# IB_V2_MOSFET.net
KiCad netlist of a schematic drawn in Altium Designer
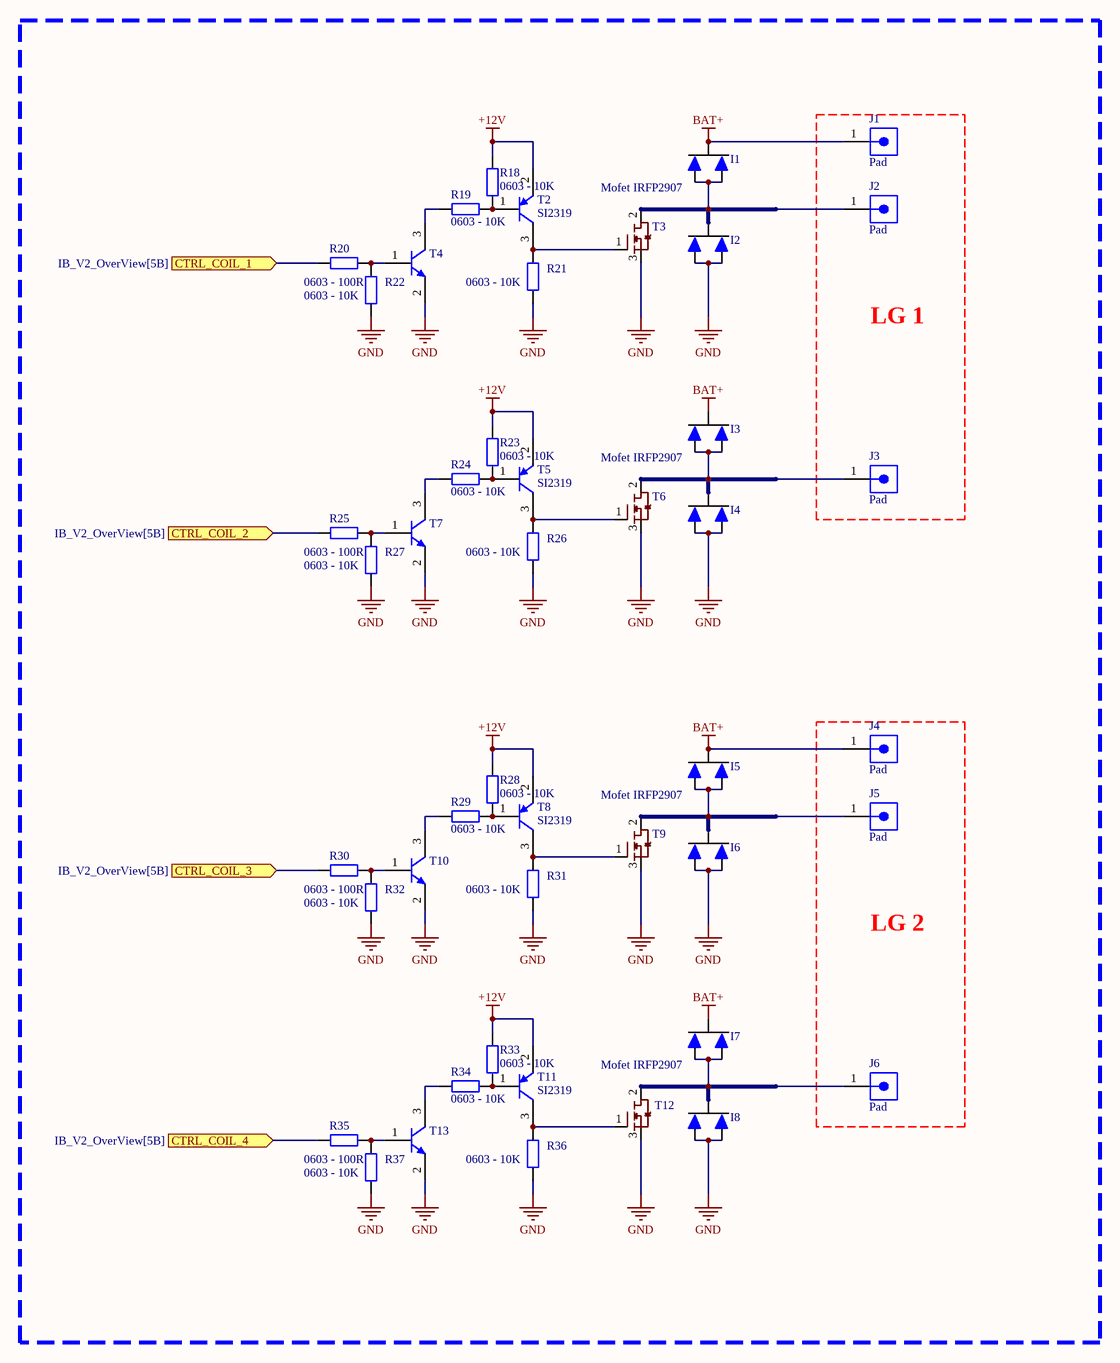
[diagram p0: IB_V2_MOSFET.SchDoc]

(export (version "E")
  (design (tool "Eeschema 10.0.6"))
  (components
    (comp (ref "I1")
      (value "12CWQ10FN")
      (footprint "TO-252")
      (description "Diode Schottky 100V 12A, SMD DPAK")
      (libsource (lib "Mach HTD-K54") (part "Diode - 12CWQ10FN"))
    )
    (comp (ref "I2")
      (value "12CWQ10FN")
      (footprint "TO-252")
      (description "Diode Schottky 100V 12A, SMD DPAK")
      (libsource (lib "Mach HTD-K54") (part "Diode - 12CWQ10FN"))
    )
    (comp (ref "I3")
      (value "12CWQ10FN")
      (footprint "TO-252")
      (description "Diode Schottky 100V 12A, SMD DPAK")
      (libsource (lib "Mach HTD-K54") (part "Diode - 12CWQ10FN"))
    )
    (comp (ref "I4")
      (value "12CWQ10FN")
      (footprint "TO-252")
      (description "Diode Schottky 100V 12A, SMD DPAK")
      (libsource (lib "Mach HTD-K54") (part "Diode - 12CWQ10FN"))
    )
    (comp (ref "I5")
      (value "12CWQ10FN")
      (footprint "TO-252")
      (description "Diode Schottky 100V 12A, SMD DPAK")
      (libsource (lib "Mach HTD-K54") (part "Diode - 12CWQ10FN"))
    )
    (comp (ref "I6")
      (value "12CWQ10FN")
      (footprint "TO-252")
      (description "Diode Schottky 100V 12A, SMD DPAK")
      (libsource (lib "Mach HTD-K54") (part "Diode - 12CWQ10FN"))
    )
    (comp (ref "I7")
      (value "12CWQ10FN")
      (footprint "TO-252")
      (description "Diode Schottky 100V 12A, SMD DPAK")
      (libsource (lib "Mach HTD-K54") (part "Diode - 12CWQ10FN"))
    )
    (comp (ref "I8")
      (value "12CWQ10FN")
      (footprint "TO-252")
      (description "Diode Schottky 100V 12A, SMD DPAK")
      (libsource (lib "Mach HTD-K54") (part "Diode - 12CWQ10FN"))
    )
    (comp (ref "J1")
      (value "Pad")
      (footprint "pad_4.5x4.5_hole_2.5mm")
      (fields (field (name "PUBLISHER") "Altium Limited"))
      (libsource (lib "MinhTien_SCHLib") (part "Pad"))
    )
    (comp (ref "J2")
      (value "Pad")
      (footprint "pad_4.5x4.5_hole_2.5mm")
      (fields (field (name "PUBLISHER") "Altium Limited"))
      (libsource (lib "MinhTien_SCHLib") (part "Pad"))
    )
    (comp (ref "J3")
      (value "Pad")
      (footprint "pad_4.5x4.5_hole_2.5mm")
      (fields (field (name "PUBLISHER") "Altium Limited"))
      (libsource (lib "MinhTien_SCHLib") (part "Pad"))
    )
    (comp (ref "J4")
      (value "Pad")
      (footprint "pad_4.5x4.5_hole_2.5mm")
      (fields (field (name "PUBLISHER") "Altium Limited"))
      (libsource (lib "MinhTien_SCHLib") (part "Pad"))
    )
    (comp (ref "J5")
      (value "Pad")
      (footprint "pad_4.5x4.5_hole_2.5mm")
      (fields (field (name "PUBLISHER") "Altium Limited"))
      (libsource (lib "MinhTien_SCHLib") (part "Pad"))
    )
    (comp (ref "J6")
      (value "Pad")
      (footprint "pad_4.5x4.5_hole_2.5mm")
      (fields (field (name "PUBLISHER") "Altium Limited"))
      (libsource (lib "MinhTien_SCHLib") (part "Pad"))
    )
    (comp (ref "R18")
      (value "0603 - 10K")
      (footprint "tro smd 0603")
      (description "Dán")
      (libsource (lib "Altium_Lib_by_KhueNguyenCreator") (part "Tro 0603 1% 680R"))
    )
    (comp (ref "R19")
      (value "0603 - 10K")
      (footprint "tro smd 0603")
      (description "Dán")
      (libsource (lib "Altium_Lib_by_KhueNguyenCreator") (part "Tro 0603 1% 680R"))
    )
    (comp (ref "R20")
      (value "0603 - 100R")
      (footprint "tro smd 0603")
      (description "Dán")
      (libsource (lib "Altium_Lib_by_KhueNguyenCreator") (part "Tro 0603 1% 680R"))
    )
    (comp (ref "R21")
      (value "0603 - 10K")
      (footprint "tro smd 0603")
      (description "Dán")
      (libsource (lib "Altium_Lib_by_KhueNguyenCreator") (part "Tro 0603 1% 680R"))
    )
    (comp (ref "R22")
      (value "0603 - 10K")
      (footprint "tro smd 0603")
      (description "Dán")
      (libsource (lib "Altium_Lib_by_KhueNguyenCreator") (part "Tro 0603 1% 680R"))
    )
    (comp (ref "R23")
      (value "0603 - 10K")
      (footprint "tro smd 0603")
      (description "Dán")
      (libsource (lib "Altium_Lib_by_KhueNguyenCreator") (part "Tro 0603 1% 680R"))
    )
    (comp (ref "R24")
      (value "0603 - 10K")
      (footprint "tro smd 0603")
      (description "Dán")
      (libsource (lib "Altium_Lib_by_KhueNguyenCreator") (part "Tro 0603 1% 680R"))
    )
    (comp (ref "R25")
      (value "0603 - 100R")
      (footprint "tro smd 0603")
      (description "Dán")
      (libsource (lib "Altium_Lib_by_KhueNguyenCreator") (part "Tro 0603 1% 680R"))
    )
    (comp (ref "R26")
      (value "0603 - 10K")
      (footprint "tro smd 0603")
      (description "Dán")
      (libsource (lib "Altium_Lib_by_KhueNguyenCreator") (part "Tro 0603 1% 680R"))
    )
    (comp (ref "R27")
      (value "0603 - 10K")
      (footprint "tro smd 0603")
      (description "Dán")
      (libsource (lib "Altium_Lib_by_KhueNguyenCreator") (part "Tro 0603 1% 680R"))
    )
    (comp (ref "R28")
      (value "0603 - 10K")
      (footprint "tro smd 0603")
      (description "Dán")
      (libsource (lib "Altium_Lib_by_KhueNguyenCreator") (part "Tro 0603 1% 680R"))
    )
    (comp (ref "R29")
      (value "0603 - 10K")
      (footprint "tro smd 0603")
      (description "Dán")
      (libsource (lib "Altium_Lib_by_KhueNguyenCreator") (part "Tro 0603 1% 680R"))
    )
    (comp (ref "R30")
      (value "0603 - 100R")
      (footprint "tro smd 0603")
      (description "Dán")
      (libsource (lib "Altium_Lib_by_KhueNguyenCreator") (part "Tro 0603 1% 680R"))
    )
    (comp (ref "R31")
      (value "0603 - 10K")
      (footprint "tro smd 0603")
      (description "Dán")
      (libsource (lib "Altium_Lib_by_KhueNguyenCreator") (part "Tro 0603 1% 680R"))
    )
    (comp (ref "R32")
      (value "0603 - 10K")
      (footprint "tro smd 0603")
      (description "Dán")
      (libsource (lib "Altium_Lib_by_KhueNguyenCreator") (part "Tro 0603 1% 680R"))
    )
    (comp (ref "R33")
      (value "0603 - 10K")
      (footprint "tro smd 0603")
      (description "Dán")
      (libsource (lib "Altium_Lib_by_KhueNguyenCreator") (part "Tro 0603 1% 680R"))
    )
    (comp (ref "R34")
      (value "0603 - 10K")
      (footprint "tro smd 0603")
      (description "Dán")
      (libsource (lib "Altium_Lib_by_KhueNguyenCreator") (part "Tro 0603 1% 680R"))
    )
    (comp (ref "R35")
      (value "0603 - 100R")
      (footprint "tro smd 0603")
      (description "Dán")
      (libsource (lib "Altium_Lib_by_KhueNguyenCreator") (part "Tro 0603 1% 680R"))
    )
    (comp (ref "R36")
      (value "0603 - 10K")
      (footprint "tro smd 0603")
      (description "Dán")
      (libsource (lib "Altium_Lib_by_KhueNguyenCreator") (part "Tro 0603 1% 680R"))
    )
    (comp (ref "R37")
      (value "0603 - 10K")
      (footprint "tro smd 0603")
      (description "Dán")
      (libsource (lib "Altium_Lib_by_KhueNguyenCreator") (part "Tro 0603 1% 680R"))
    )
    (comp (ref "T2")
      (value "SI2319")
      (footprint "SOT - 23")
      (description "P-Channel 40-V(D-S) MOSEFET\r\nSOT-23/3 LEAD")
      (libsource (lib "HTD-AK") (part "Transistor - A1015"))
    )
    (comp (ref "T3")
      (value "Mofet IRFP2907")
      (footprint "TO 247 AC")
      (libsource (lib "TG21_SCHLib") (part "IRFP2907"))
    )
    (comp (ref "T4")
      (value "MMBT2222A 1P Transistor NPN")
      (footprint "SOT - 23")
      (description "Transistor NPN 40V 0.6A 3 Chân SOT-23/3 LEAD")
      (libsource (lib "HTD-AK") (part "Transistor - 2N2222"))
    )
    (comp (ref "T5")
      (value "SI2319")
      (footprint "SOT - 23")
      (description "P-Channel 40-V(D-S) MOSEFET\r\nSOT-23/3 LEAD")
      (libsource (lib "HTD-AK") (part "Transistor - A1015"))
    )
    (comp (ref "T6")
      (value "Mofet IRFP2907")
      (footprint "TO 247 AC")
      (libsource (lib "TG21_SCHLib") (part "IRFP2907"))
    )
    (comp (ref "T7")
      (value "MMBT2222A 1P Transistor NPN")
      (footprint "SOT - 23")
      (description "Transistor NPN 40V 0.6A 3 Chân SOT-23/3 LEAD")
      (libsource (lib "HTD-AK") (part "Transistor - 2N2222"))
    )
    (comp (ref "T8")
      (value "SI2319")
      (footprint "SOT - 23")
      (description "P-Channel 40-V(D-S) MOSEFET\r\nSOT-23/3 LEAD")
      (libsource (lib "HTD-AK") (part "Transistor - A1015"))
    )
    (comp (ref "T9")
      (value "Mofet IRFP2907")
      (footprint "TO 247 AC")
      (libsource (lib "TG21_SCHLib") (part "IRFP2907"))
    )
    (comp (ref "T10")
      (value "MMBT2222A 1P Transistor NPN")
      (footprint "SOT - 23")
      (description "Transistor NPN 40V 0.6A 3 Chân SOT-23/3 LEAD")
      (libsource (lib "HTD-AK") (part "Transistor - 2N2222"))
    )
    (comp (ref "T11")
      (value "SI2319")
      (footprint "SOT - 23")
      (description "P-Channel 40-V(D-S) MOSEFET\r\nSOT-23/3 LEAD")
      (libsource (lib "HTD-AK") (part "Transistor - A1015"))
    )
    (comp (ref "T12")
      (value "Mofet IRFP2907")
      (footprint "TO 247 AC")
      (libsource (lib "TG21_SCHLib") (part "IRFP2907"))
    )
    (comp (ref "T13")
      (value "MMBT2222A 1P Transistor NPN")
      (footprint "SOT - 23")
      (description "Transistor NPN 40V 0.6A 3 Chân SOT-23/3 LEAD")
      (libsource (lib "HTD-AK") (part "Transistor - 2N2222"))
    )
  )
  (nets
    (net (code "1") (name "+12V") (class "Default")
      (node (ref "R18") (pin "1") (pinfunction "1_1") (pintype "passive"))
      (node (ref "R23") (pin "1") (pinfunction "1_1") (pintype "passive"))
      (node (ref "R28") (pin "1") (pinfunction "1_1") (pintype "passive"))
      (node (ref "R33") (pin "1") (pinfunction "1_1") (pintype "passive"))
      (node (ref "T11") (pin "2") (pinfunction "E_2") (pintype "passive"))
      (node (ref "T2") (pin "2") (pinfunction "E_2") (pintype "passive"))
      (node (ref "T5") (pin "2") (pinfunction "E_2") (pintype "passive"))
      (node (ref "T8") (pin "2") (pinfunction "E_2") (pintype "passive"))
    )
    (net (code "2") (name "/CTRL_COIL_1") (class "Default")
      (node (ref "R20") (pin "2") (pinfunction "2_2") (pintype "passive"))
    )
    (net (code "3") (name "/CTRL_COIL_2") (class "Default")
      (node (ref "R25") (pin "2") (pinfunction "2_2") (pintype "passive"))
    )
    (net (code "4") (name "/CTRL_COIL_3") (class "Default")
      (node (ref "R30") (pin "2") (pinfunction "2_2") (pintype "passive"))
    )
    (net (code "5") (name "/CTRL_COIL_4") (class "Default")
      (node (ref "R35") (pin "2") (pinfunction "2_2") (pintype "passive"))
    )
    (net (code "6") (name "BAT+") (class "Default")
      (node (ref "I1") (pin "2") (pinfunction "Ktot_2") (pintype "passive"))
      (node (ref "I3") (pin "2") (pinfunction "Ktot_2") (pintype "passive"))
      (node (ref "I5") (pin "2") (pinfunction "Ktot_2") (pintype "passive"))
      (node (ref "I7") (pin "2") (pinfunction "Ktot_2") (pintype "passive"))
      (node (ref "J1") (pin "1") (pinfunction "1_1") (pintype "passive"))
      (node (ref "J4") (pin "1") (pinfunction "1_1") (pintype "passive"))
    )
    (net (code "7") (name "GND") (class "Default")
      (node (ref "I2") (pin "1") (pinfunction "Anot_1") (pintype "passive"))
      (node (ref "I2") (pin "3") (pinfunction "Anot_3") (pintype "passive"))
      (node (ref "I4") (pin "1") (pinfunction "Anot_1") (pintype "passive"))
      (node (ref "I4") (pin "3") (pinfunction "Anot_3") (pintype "passive"))
      (node (ref "I6") (pin "1") (pinfunction "Anot_1") (pintype "passive"))
      (node (ref "I6") (pin "3") (pinfunction "Anot_3") (pintype "passive"))
      (node (ref "I8") (pin "1") (pinfunction "Anot_1") (pintype "passive"))
      (node (ref "I8") (pin "3") (pinfunction "Anot_3") (pintype "passive"))
      (node (ref "R21") (pin "1") (pinfunction "1_1") (pintype "passive"))
      (node (ref "R22") (pin "1") (pinfunction "1_1") (pintype "passive"))
      (node (ref "R26") (pin "1") (pinfunction "1_1") (pintype "passive"))
      (node (ref "R27") (pin "1") (pinfunction "1_1") (pintype "passive"))
      (node (ref "R31") (pin "1") (pinfunction "1_1") (pintype "passive"))
      (node (ref "R32") (pin "1") (pinfunction "1_1") (pintype "passive"))
      (node (ref "R36") (pin "1") (pinfunction "1_1") (pintype "passive"))
      (node (ref "R37") (pin "1") (pinfunction "1_1") (pintype "passive"))
      (node (ref "T10") (pin "2") (pinfunction "E_2") (pintype "passive"))
      (node (ref "T12") (pin "3") (pinfunction "S_3") (pintype "passive"))
      (node (ref "T13") (pin "2") (pinfunction "E_2") (pintype "passive"))
      (node (ref "T3") (pin "3") (pinfunction "S_3") (pintype "passive"))
      (node (ref "T4") (pin "2") (pinfunction "E_2") (pintype "passive"))
      (node (ref "T6") (pin "3") (pinfunction "S_3") (pintype "passive"))
      (node (ref "T7") (pin "2") (pinfunction "E_2") (pintype "passive"))
      (node (ref "T9") (pin "3") (pinfunction "S_3") (pintype "passive"))
    )
    (net (code "8") (name "Net-(I2-Ktot)") (class "Default")
      (node (ref "I1") (pin "1") (pinfunction "Anot_1") (pintype "passive"))
      (node (ref "I1") (pin "3") (pinfunction "Anot_3") (pintype "passive"))
      (node (ref "I2") (pin "2") (pinfunction "Ktot_2") (pintype "passive"))
      (node (ref "J2") (pin "1") (pinfunction "1_1") (pintype "passive"))
      (node (ref "T3") (pin "2") (pinfunction "D_2") (pintype "passive"))
    )
    (net (code "9") (name "Net-(I4-Ktot)") (class "Default")
      (node (ref "I3") (pin "1") (pinfunction "Anot_1") (pintype "passive"))
      (node (ref "I3") (pin "3") (pinfunction "Anot_3") (pintype "passive"))
      (node (ref "I4") (pin "2") (pinfunction "Ktot_2") (pintype "passive"))
      (node (ref "J3") (pin "1") (pinfunction "1_1") (pintype "passive"))
      (node (ref "T6") (pin "2") (pinfunction "D_2") (pintype "passive"))
    )
    (net (code "10") (name "Net-(I6-Ktot)") (class "Default")
      (node (ref "I5") (pin "1") (pinfunction "Anot_1") (pintype "passive"))
      (node (ref "I5") (pin "3") (pinfunction "Anot_3") (pintype "passive"))
      (node (ref "I6") (pin "2") (pinfunction "Ktot_2") (pintype "passive"))
      (node (ref "J5") (pin "1") (pinfunction "1_1") (pintype "passive"))
      (node (ref "T9") (pin "2") (pinfunction "D_2") (pintype "passive"))
    )
    (net (code "11") (name "Net-(I8-Ktot)") (class "Default")
      (node (ref "I7") (pin "1") (pinfunction "Anot_1") (pintype "passive"))
      (node (ref "I7") (pin "3") (pinfunction "Anot_3") (pintype "passive"))
      (node (ref "I8") (pin "2") (pinfunction "Ktot_2") (pintype "passive"))
      (node (ref "J6") (pin "1") (pinfunction "1_1") (pintype "passive"))
      (node (ref "T12") (pin "2") (pinfunction "D_2") (pintype "passive"))
    )
    (net (code "12") (name "Net-(T2-B)") (class "Default")
      (node (ref "R18") (pin "2") (pinfunction "2_2") (pintype "passive"))
      (node (ref "R19") (pin "1") (pinfunction "1_1") (pintype "passive"))
      (node (ref "T2") (pin "1") (pinfunction "B_1") (pintype "passive"))
    )
    (net (code "13") (name "Net-(T2-C)") (class "Default")
      (node (ref "R21") (pin "2") (pinfunction "2_2") (pintype "passive"))
      (node (ref "T2") (pin "3") (pinfunction "C_3") (pintype "passive"))
      (node (ref "T3") (pin "1") (pinfunction "G_1") (pintype "passive"))
    )
    (net (code "14") (name "Net-(T4-B)") (class "Default")
      (node (ref "R20") (pin "1") (pinfunction "1_1") (pintype "passive"))
      (node (ref "R22") (pin "2") (pinfunction "2_2") (pintype "passive"))
      (node (ref "T4") (pin "1") (pinfunction "B_1") (pintype "passive"))
    )
    (net (code "15") (name "Net-(T4-C)") (class "Default")
      (node (ref "R19") (pin "2") (pinfunction "2_2") (pintype "passive"))
      (node (ref "T4") (pin "3") (pinfunction "C_3") (pintype "passive"))
    )
    (net (code "16") (name "Net-(T5-B)") (class "Default")
      (node (ref "R23") (pin "2") (pinfunction "2_2") (pintype "passive"))
      (node (ref "R24") (pin "1") (pinfunction "1_1") (pintype "passive"))
      (node (ref "T5") (pin "1") (pinfunction "B_1") (pintype "passive"))
    )
    (net (code "17") (name "Net-(T5-C)") (class "Default")
      (node (ref "R26") (pin "2") (pinfunction "2_2") (pintype "passive"))
      (node (ref "T5") (pin "3") (pinfunction "C_3") (pintype "passive"))
      (node (ref "T6") (pin "1") (pinfunction "G_1") (pintype "passive"))
    )
    (net (code "18") (name "Net-(T7-B)") (class "Default")
      (node (ref "R25") (pin "1") (pinfunction "1_1") (pintype "passive"))
      (node (ref "R27") (pin "2") (pinfunction "2_2") (pintype "passive"))
      (node (ref "T7") (pin "1") (pinfunction "B_1") (pintype "passive"))
    )
    (net (code "19") (name "Net-(T7-C)") (class "Default")
      (node (ref "R24") (pin "2") (pinfunction "2_2") (pintype "passive"))
      (node (ref "T7") (pin "3") (pinfunction "C_3") (pintype "passive"))
    )
    (net (code "20") (name "Net-(T8-B)") (class "Default")
      (node (ref "R28") (pin "2") (pinfunction "2_2") (pintype "passive"))
      (node (ref "R29") (pin "1") (pinfunction "1_1") (pintype "passive"))
      (node (ref "T8") (pin "1") (pinfunction "B_1") (pintype "passive"))
    )
    (net (code "21") (name "Net-(T8-C)") (class "Default")
      (node (ref "R31") (pin "2") (pinfunction "2_2") (pintype "passive"))
      (node (ref "T8") (pin "3") (pinfunction "C_3") (pintype "passive"))
      (node (ref "T9") (pin "1") (pinfunction "G_1") (pintype "passive"))
    )
    (net (code "22") (name "Net-(T10-B)") (class "Default")
      (node (ref "R30") (pin "1") (pinfunction "1_1") (pintype "passive"))
      (node (ref "R32") (pin "2") (pinfunction "2_2") (pintype "passive"))
      (node (ref "T10") (pin "1") (pinfunction "B_1") (pintype "passive"))
    )
    (net (code "23") (name "Net-(T10-C)") (class "Default")
      (node (ref "R29") (pin "2") (pinfunction "2_2") (pintype "passive"))
      (node (ref "T10") (pin "3") (pinfunction "C_3") (pintype "passive"))
    )
    (net (code "24") (name "Net-(T11-B)") (class "Default")
      (node (ref "R33") (pin "2") (pinfunction "2_2") (pintype "passive"))
      (node (ref "R34") (pin "1") (pinfunction "1_1") (pintype "passive"))
      (node (ref "T11") (pin "1") (pinfunction "B_1") (pintype "passive"))
    )
    (net (code "25") (name "Net-(T11-C)") (class "Default")
      (node (ref "R36") (pin "2") (pinfunction "2_2") (pintype "passive"))
      (node (ref "T11") (pin "3") (pinfunction "C_3") (pintype "passive"))
      (node (ref "T12") (pin "1") (pinfunction "G_1") (pintype "passive"))
    )
    (net (code "26") (name "Net-(T13-B)") (class "Default")
      (node (ref "R35") (pin "1") (pinfunction "1_1") (pintype "passive"))
      (node (ref "R37") (pin "2") (pinfunction "2_2") (pintype "passive"))
      (node (ref "T13") (pin "1") (pinfunction "B_1") (pintype "passive"))
    )
    (net (code "27") (name "Net-(T13-C)") (class "Default")
      (node (ref "R34") (pin "2") (pinfunction "2_2") (pintype "passive"))
      (node (ref "T13") (pin "3") (pinfunction "C_3") (pintype "passive"))
    )
  )
)
